# schematics.net
KiCad netlist of a schematic drawn in EAGLE
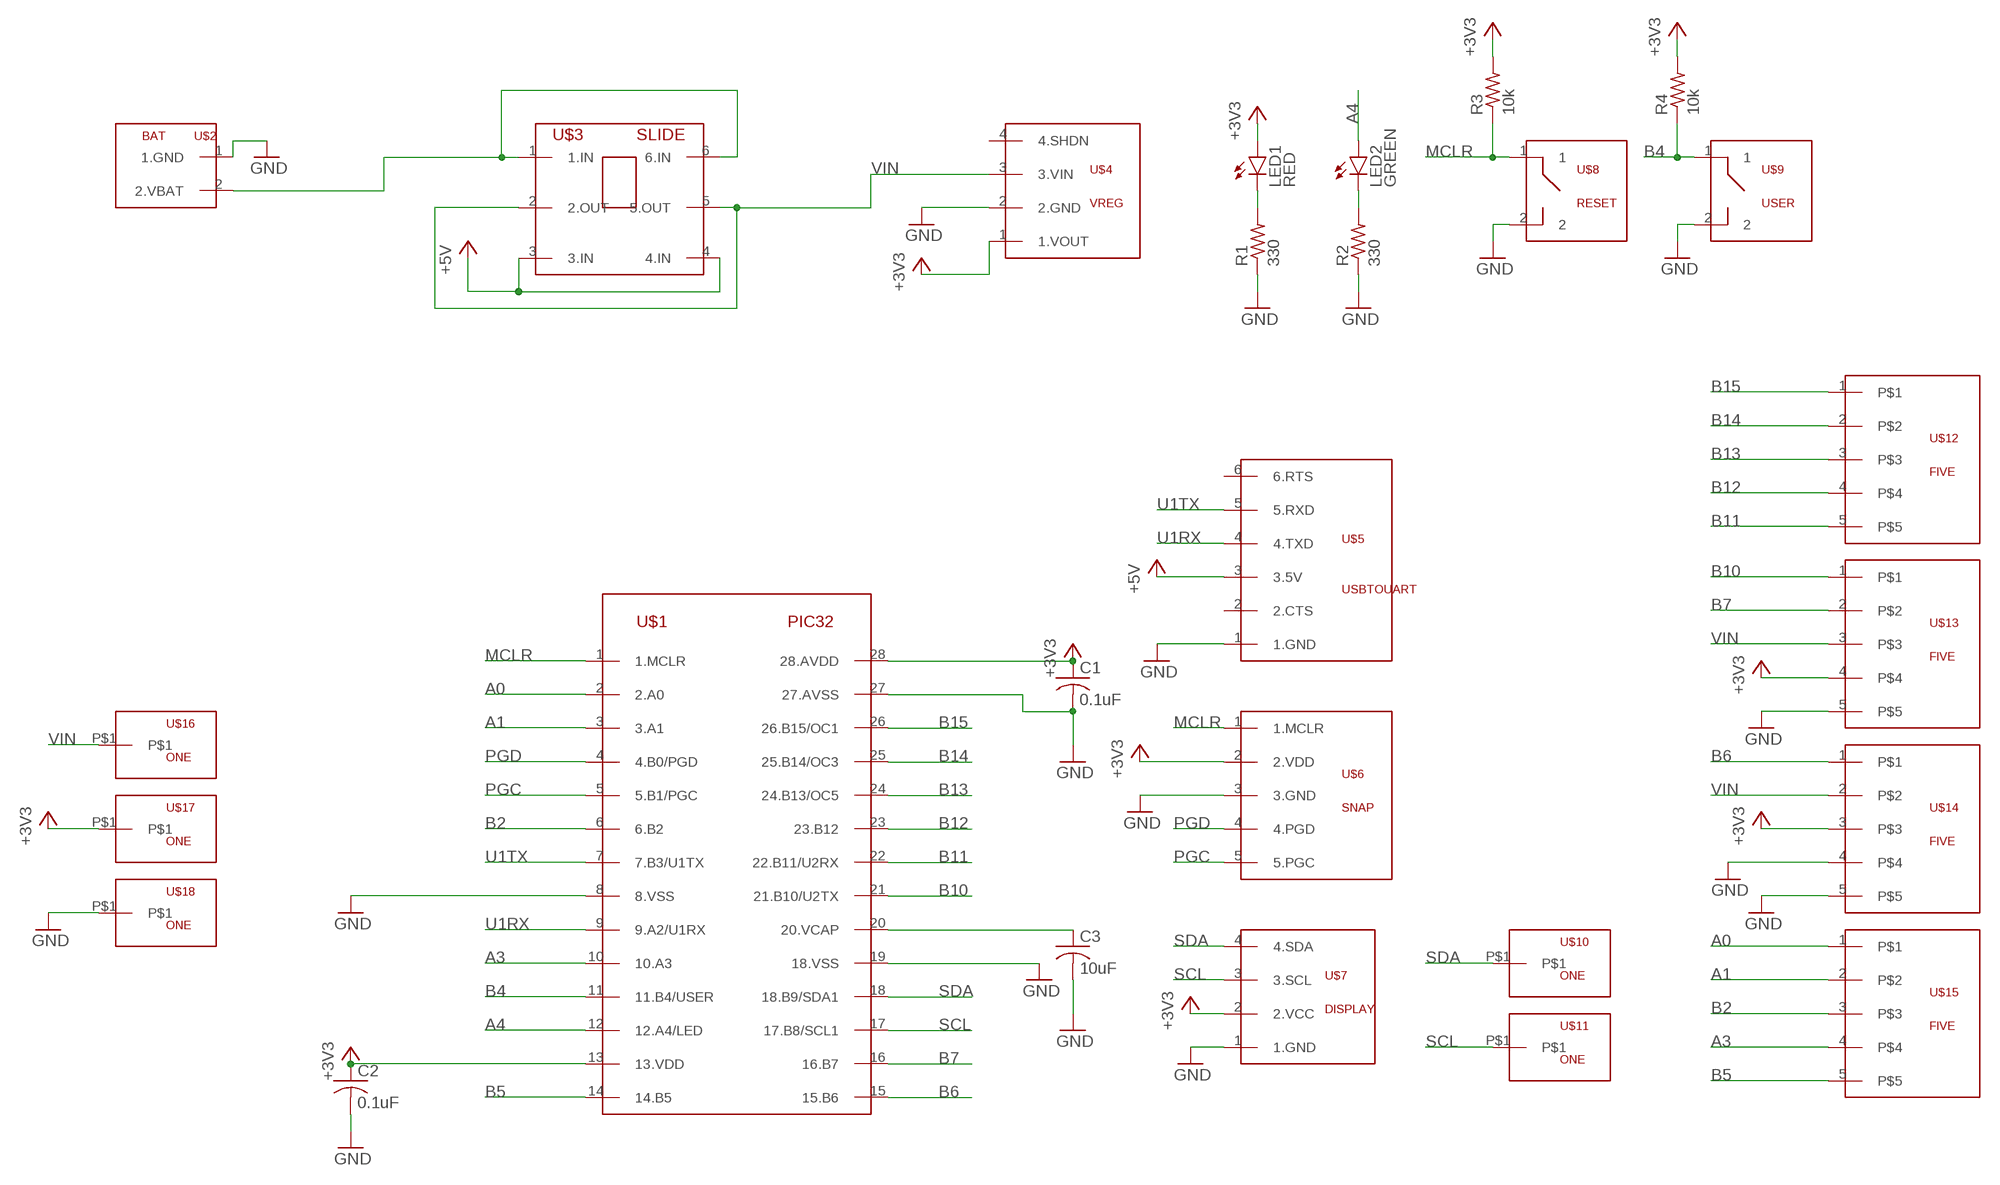
[diagram p0: schematic, sheet 1]

(export (version "E")
  (design (tool "Eeschema 10.0.6"))
  (components
    (comp (ref "C1")
      (value "0.1uF")
      (footprint "eagle-import:C025-024X044")
      (libsource (lib "eagle-import") (part "C-US025-024X044"))
    )
    (comp (ref "C2")
      (value "0.1uF")
      (footprint "eagle-import:C025-024X044")
      (libsource (lib "eagle-import") (part "C-US025-024X044"))
    )
    (comp (ref "C3")
      (value "10uF")
      (footprint "eagle-import:C025-024X044")
      (libsource (lib "eagle-import") (part "C-US025-024X044"))
    )
    (comp (ref "LED1")
      (value "RED")
      (footprint "eagle-import:LED3MM")
      (libsource (lib "eagle-import") (part "LED3MM"))
    )
    (comp (ref "LED2")
      (value "GREEN")
      (footprint "eagle-import:LED3MM")
      (libsource (lib "eagle-import") (part "LED3MM"))
    )
    (comp (ref "R1")
      (value "330")
      (footprint "eagle-import:0207_7")
      (libsource (lib "eagle-import") (part "R-US_0207/7"))
    )
    (comp (ref "R2")
      (value "330")
      (footprint "eagle-import:0207_7")
      (libsource (lib "eagle-import") (part "R-US_0207/7"))
    )
    (comp (ref "R3")
      (value "10k")
      (footprint "eagle-import:0207_7")
      (libsource (lib "eagle-import") (part "R-US_0207/7"))
    )
    (comp (ref "R4")
      (value "10k")
      (footprint "eagle-import:0207_7")
      (libsource (lib "eagle-import") (part "R-US_0207/7"))
    )
    (comp (ref "U$1")
      (value "PIC32")
      (footprint "eagle-import:DIL28-3")
      (libsource (lib "eagle-import") (part "PIC32"))
    )
    (comp (ref "U$2")
      (value "BAT")
      (footprint "eagle-import:BAT")
      (libsource (lib "eagle-import") (part "BAT"))
    )
    (comp (ref "U$3")
      (value "SLIDE")
      (footprint "eagle-import:SLIDE")
      (libsource (lib "eagle-import") (part "SLIDE"))
    )
    (comp (ref "U$4")
      (value "VREG")
      (footprint "eagle-import:VREG")
      (libsource (lib "eagle-import") (part "VREG"))
    )
    (comp (ref "U$5")
      (value "USBTOUART")
      (footprint "eagle-import:USBTOUART")
      (libsource (lib "eagle-import") (part "USBTOUART"))
    )
    (comp (ref "U$6")
      (value "SNAP")
      (footprint "eagle-import:SNAP")
      (libsource (lib "eagle-import") (part "SNAP"))
    )
    (comp (ref "U$7")
      (value "DISPLAY")
      (footprint "eagle-import:DISPLAY")
      (libsource (lib "eagle-import") (part "DISPLAY"))
    )
    (comp (ref "U$8")
      (value "RESET")
      (footprint "eagle-import:BUTTON")
      (libsource (lib "eagle-import") (part "BUTTON"))
    )
    (comp (ref "U$9")
      (value "USER")
      (footprint "eagle-import:BUTTON")
      (libsource (lib "eagle-import") (part "BUTTON"))
    )
    (comp (ref "U$10")
      (value "ONE")
      (footprint "eagle-import:ONE")
      (libsource (lib "eagle-import") (part "ONE"))
    )
    (comp (ref "U$11")
      (value "ONE")
      (footprint "eagle-import:ONE")
      (libsource (lib "eagle-import") (part "ONE"))
    )
    (comp (ref "U$12")
      (value "FIVE")
      (footprint "eagle-import:FIVE")
      (libsource (lib "eagle-import") (part "FIVE"))
    )
    (comp (ref "U$13")
      (value "FIVE")
      (footprint "eagle-import:FIVE")
      (libsource (lib "eagle-import") (part "FIVE"))
    )
    (comp (ref "U$14")
      (value "FIVE")
      (footprint "eagle-import:FIVE")
      (libsource (lib "eagle-import") (part "FIVE"))
    )
    (comp (ref "U$15")
      (value "FIVE")
      (footprint "eagle-import:FIVE")
      (libsource (lib "eagle-import") (part "FIVE"))
    )
    (comp (ref "U$16")
      (value "ONE")
      (footprint "eagle-import:ONE")
      (libsource (lib "eagle-import") (part "ONE"))
    )
    (comp (ref "U$17")
      (value "ONE")
      (footprint "eagle-import:ONE")
      (libsource (lib "eagle-import") (part "ONE"))
    )
    (comp (ref "U$18")
      (value "ONE")
      (footprint "eagle-import:ONE")
      (libsource (lib "eagle-import") (part "ONE"))
    )
  )
  (nets
    (net (code "1") (name "+3V3") (class "Default")
      (node (ref "C1") (pin "1") (pinfunction "1_1") (pintype "passive"))
      (node (ref "C2") (pin "1") (pinfunction "1_1") (pintype "passive"))
      (node (ref "LED1") (pin "A") (pinfunction "A_A") (pintype "passive"))
      (node (ref "R3") (pin "2") (pinfunction "2_2") (pintype "passive"))
      (node (ref "R4") (pin "2") (pinfunction "2_2") (pintype "passive"))
      (node (ref "U$1") (pin "13") (pinfunction "13.VDD_13") (pintype "bidirectional"))
      (node (ref "U$1") (pin "28") (pinfunction "28.AVDD_28") (pintype "bidirectional"))
      (node (ref "U$13") (pin "4") (pinfunction "P$4_4") (pintype "bidirectional"))
      (node (ref "U$14") (pin "3") (pinfunction "P$3_3") (pintype "bidirectional"))
      (node (ref "U$17") (pin "P$1") (pinfunction "P$1_P$1") (pintype "bidirectional"))
      (node (ref "U$4") (pin "1") (pinfunction "1.VOUT_1") (pintype "bidirectional"))
      (node (ref "U$6") (pin "2") (pinfunction "2.VDD_2") (pintype "bidirectional"))
      (node (ref "U$7") (pin "2") (pinfunction "2.VCC_2") (pintype "bidirectional"))
    )
    (net (code "2") (name "+5V") (class "Default")
      (node (ref "U$3") (pin "3") (pinfunction "3.IN_3") (pintype "bidirectional"))
      (node (ref "U$3") (pin "4") (pinfunction "4.IN_4") (pintype "bidirectional"))
      (node (ref "U$5") (pin "3") (pinfunction "3.5V_3") (pintype "bidirectional"))
    )
    (net (code "3") (name "/A0") (class "Default")
      (node (ref "U$1") (pin "2") (pinfunction "2.A0_2") (pintype "bidirectional"))
      (node (ref "U$15") (pin "1") (pinfunction "P$1_1") (pintype "bidirectional"))
    )
    (net (code "4") (name "/A1") (class "Default")
      (node (ref "U$1") (pin "3") (pinfunction "3.A1_3") (pintype "bidirectional"))
      (node (ref "U$15") (pin "2") (pinfunction "P$2_2") (pintype "bidirectional"))
    )
    (net (code "5") (name "/A3") (class "Default")
      (node (ref "U$1") (pin "10") (pinfunction "10.A3_10") (pintype "bidirectional"))
      (node (ref "U$15") (pin "4") (pinfunction "P$4_4") (pintype "bidirectional"))
    )
    (net (code "6") (name "/A4") (class "Default")
      (node (ref "LED2") (pin "A") (pinfunction "A_A") (pintype "passive"))
      (node (ref "U$1") (pin "12") (pinfunction "12.A4/LED_12") (pintype "bidirectional"))
    )
    (net (code "7") (name "/B2") (class "Default")
      (node (ref "U$1") (pin "6") (pinfunction "6.B2_6") (pintype "bidirectional"))
      (node (ref "U$15") (pin "3") (pinfunction "P$3_3") (pintype "bidirectional"))
    )
    (net (code "8") (name "/B4") (class "Default")
      (node (ref "R4") (pin "1") (pinfunction "1_1") (pintype "passive"))
      (node (ref "U$1") (pin "11") (pinfunction "11.B4/USER_11") (pintype "bidirectional"))
      (node (ref "U$9") (pin "1") (pinfunction "1_1") (pintype "bidirectional"))
    )
    (net (code "9") (name "/B5") (class "Default")
      (node (ref "U$1") (pin "14") (pinfunction "14.B5_14") (pintype "bidirectional"))
      (node (ref "U$15") (pin "5") (pinfunction "P$5_5") (pintype "bidirectional"))
    )
    (net (code "10") (name "/B6") (class "Default")
      (node (ref "U$1") (pin "15") (pinfunction "15.B6_15") (pintype "bidirectional"))
      (node (ref "U$14") (pin "1") (pinfunction "P$1_1") (pintype "bidirectional"))
    )
    (net (code "11") (name "/B7") (class "Default")
      (node (ref "U$1") (pin "16") (pinfunction "16.B7_16") (pintype "bidirectional"))
      (node (ref "U$13") (pin "2") (pinfunction "P$2_2") (pintype "bidirectional"))
    )
    (net (code "12") (name "/B10") (class "Default")
      (node (ref "U$1") (pin "21") (pinfunction "21.B10/U2TX_21") (pintype "bidirectional"))
      (node (ref "U$13") (pin "1") (pinfunction "P$1_1") (pintype "bidirectional"))
    )
    (net (code "13") (name "/B11") (class "Default")
      (node (ref "U$1") (pin "22") (pinfunction "22.B11/U2RX_22") (pintype "bidirectional"))
      (node (ref "U$12") (pin "5") (pinfunction "P$5_5") (pintype "bidirectional"))
    )
    (net (code "14") (name "/B12") (class "Default")
      (node (ref "U$1") (pin "23") (pinfunction "23.B12_23") (pintype "bidirectional"))
      (node (ref "U$12") (pin "4") (pinfunction "P$4_4") (pintype "bidirectional"))
    )
    (net (code "15") (name "/B13") (class "Default")
      (node (ref "U$1") (pin "24") (pinfunction "24.B13/OC5_24") (pintype "bidirectional"))
      (node (ref "U$12") (pin "3") (pinfunction "P$3_3") (pintype "bidirectional"))
    )
    (net (code "16") (name "/B14") (class "Default")
      (node (ref "U$1") (pin "25") (pinfunction "25.B14/OC3_25") (pintype "bidirectional"))
      (node (ref "U$12") (pin "2") (pinfunction "P$2_2") (pintype "bidirectional"))
    )
    (net (code "17") (name "/B15") (class "Default")
      (node (ref "U$1") (pin "26") (pinfunction "26.B15/OC1_26") (pintype "bidirectional"))
      (node (ref "U$12") (pin "1") (pinfunction "P$1_1") (pintype "bidirectional"))
    )
    (net (code "18") (name "/MCLR") (class "Default")
      (node (ref "R3") (pin "1") (pinfunction "1_1") (pintype "passive"))
      (node (ref "U$1") (pin "1") (pinfunction "1.MCLR_1") (pintype "bidirectional"))
      (node (ref "U$6") (pin "1") (pinfunction "1.MCLR_1") (pintype "bidirectional"))
      (node (ref "U$8") (pin "1") (pinfunction "1_1") (pintype "bidirectional"))
    )
    (net (code "19") (name "/PGC") (class "Default")
      (node (ref "U$1") (pin "5") (pinfunction "5.B1/PGC_5") (pintype "bidirectional"))
      (node (ref "U$6") (pin "5") (pinfunction "5.PGC_5") (pintype "bidirectional"))
    )
    (net (code "20") (name "/PGD") (class "Default")
      (node (ref "U$1") (pin "4") (pinfunction "4.B0/PGD_4") (pintype "bidirectional"))
      (node (ref "U$6") (pin "4") (pinfunction "4.PGD_4") (pintype "bidirectional"))
    )
    (net (code "21") (name "/SCL") (class "Default")
      (node (ref "U$1") (pin "17") (pinfunction "17.B8/SCL1_17") (pintype "bidirectional"))
      (node (ref "U$11") (pin "P$1") (pinfunction "P$1_P$1") (pintype "bidirectional"))
      (node (ref "U$7") (pin "3") (pinfunction "3.SCL_3") (pintype "bidirectional"))
    )
    (net (code "22") (name "/SDA") (class "Default")
      (node (ref "U$1") (pin "18") (pinfunction "18.B9/SDA1_18") (pintype "bidirectional"))
      (node (ref "U$10") (pin "P$1") (pinfunction "P$1_P$1") (pintype "bidirectional"))
      (node (ref "U$7") (pin "4") (pinfunction "4.SDA_4") (pintype "bidirectional"))
    )
    (net (code "23") (name "/U1RX") (class "Default")
      (node (ref "U$1") (pin "9") (pinfunction "9.A2/U1RX_9") (pintype "bidirectional"))
      (node (ref "U$5") (pin "4") (pinfunction "4.TXD_4") (pintype "bidirectional"))
    )
    (net (code "24") (name "/U1TX") (class "Default")
      (node (ref "U$1") (pin "7") (pinfunction "7.B3/U1TX_7") (pintype "bidirectional"))
      (node (ref "U$5") (pin "5") (pinfunction "5.RXD_5") (pintype "bidirectional"))
    )
    (net (code "25") (name "/VIN") (class "Default")
      (node (ref "U$13") (pin "3") (pinfunction "P$3_3") (pintype "bidirectional"))
      (node (ref "U$14") (pin "2") (pinfunction "P$2_2") (pintype "bidirectional"))
      (node (ref "U$16") (pin "P$1") (pinfunction "P$1_P$1") (pintype "bidirectional"))
      (node (ref "U$3") (pin "2") (pinfunction "2.OUT_2") (pintype "bidirectional"))
      (node (ref "U$3") (pin "5") (pinfunction "5.OUT_5") (pintype "bidirectional"))
      (node (ref "U$4") (pin "3") (pinfunction "3.VIN_3") (pintype "bidirectional"))
    )
    (net (code "26") (name "GND") (class "Default")
      (node (ref "C1") (pin "2") (pinfunction "2_2") (pintype "passive"))
      (node (ref "C2") (pin "2") (pinfunction "2_2") (pintype "passive"))
      (node (ref "C3") (pin "2") (pinfunction "2_2") (pintype "passive"))
      (node (ref "R1") (pin "1") (pinfunction "1_1") (pintype "passive"))
      (node (ref "R2") (pin "1") (pinfunction "1_1") (pintype "passive"))
      (node (ref "U$1") (pin "19") (pinfunction "18.VSS_19") (pintype "bidirectional"))
      (node (ref "U$1") (pin "27") (pinfunction "27.AVSS_27") (pintype "bidirectional"))
      (node (ref "U$1") (pin "8") (pinfunction "8.VSS_8") (pintype "bidirectional"))
      (node (ref "U$13") (pin "5") (pinfunction "P$5_5") (pintype "bidirectional"))
      (node (ref "U$14") (pin "4") (pinfunction "P$4_4") (pintype "bidirectional"))
      (node (ref "U$14") (pin "5") (pinfunction "P$5_5") (pintype "bidirectional"))
      (node (ref "U$18") (pin "P$1") (pinfunction "P$1_P$1") (pintype "bidirectional"))
      (node (ref "U$2") (pin "1") (pinfunction "1.GND_1") (pintype "bidirectional"))
      (node (ref "U$4") (pin "2") (pinfunction "2.GND_2") (pintype "bidirectional"))
      (node (ref "U$5") (pin "1") (pinfunction "1.GND_1") (pintype "bidirectional"))
      (node (ref "U$6") (pin "3") (pinfunction "3.GND_3") (pintype "bidirectional"))
      (node (ref "U$7") (pin "1") (pinfunction "1.GND_1") (pintype "bidirectional"))
      (node (ref "U$8") (pin "2") (pinfunction "2_2") (pintype "bidirectional"))
      (node (ref "U$9") (pin "2") (pinfunction "2_2") (pintype "bidirectional"))
    )
    (net (code "27") (name "Net-(LED1-C)") (class "Default")
      (node (ref "LED1") (pin "K") (pinfunction "C_K") (pintype "passive"))
      (node (ref "R1") (pin "2") (pinfunction "2_2") (pintype "passive"))
    )
    (net (code "28") (name "Net-(LED2-C)") (class "Default")
      (node (ref "LED2") (pin "K") (pinfunction "C_K") (pintype "passive"))
      (node (ref "R2") (pin "2") (pinfunction "2_2") (pintype "passive"))
    )
    (net (code "29") (name "Net-(U$1-20.VCAP)") (class "Default")
      (node (ref "C3") (pin "1") (pinfunction "1_1") (pintype "passive"))
      (node (ref "U$1") (pin "20") (pinfunction "20.VCAP_20") (pintype "bidirectional"))
    )
    (net (code "30") (name "Net-(U$2-2.VBAT)") (class "Default")
      (node (ref "U$2") (pin "2") (pinfunction "2.VBAT_2") (pintype "bidirectional"))
      (node (ref "U$3") (pin "1") (pinfunction "1.IN_1") (pintype "bidirectional"))
      (node (ref "U$3") (pin "6") (pinfunction "6.IN_6") (pintype "bidirectional"))
    )
    (net (code "31") (name "unconnected-(U$4-4.SHDN-Pad4)") (class "Default")
      (node (ref "U$4") (pin "4") (pinfunction "4.SHDN_4") (pintype "bidirectional"))
    )
    (net (code "32") (name "unconnected-(U$5-2.CTS-Pad2)") (class "Default")
      (node (ref "U$5") (pin "2") (pinfunction "2.CTS_2") (pintype "bidirectional"))
    )
    (net (code "33") (name "unconnected-(U$5-6.RTS-Pad6)") (class "Default")
      (node (ref "U$5") (pin "6") (pinfunction "6.RTS_6") (pintype "bidirectional"))
    )
  )
)
